# USBC.net
KiCad netlist of a schematic drawn in Altium Designer
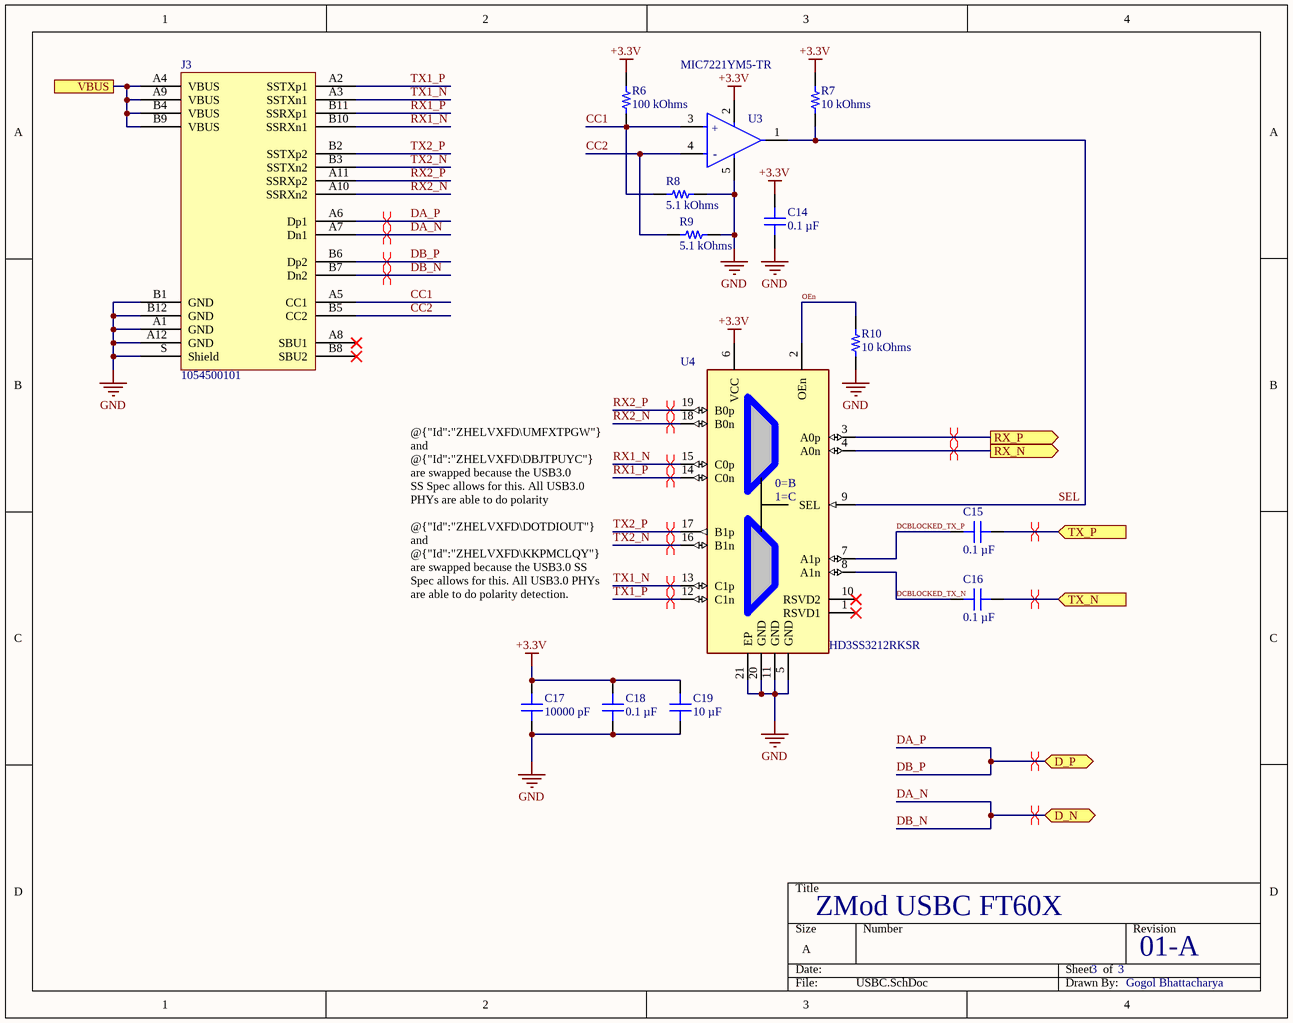
[diagram p0: USBC.SchDoc]

(export (version "E")
  (design (tool "Eeschema 10.0.6"))
  (components
    (comp (ref "C14")
      (value "0.1 µF")
      (footprint "CAP 0603_1608")
      (description "CAP CER 0.1UF 50V X7R 0603")
      (fields (field (name "PART NUMBER") "C0603C104K5RAC7411") (field (name "MANUFACTURER") "KEMET"))
      (libsource (lib "Celestial Altium Library - altium_library") (part "Capacitor"))
    )
    (comp (ref "C15")
      (value "0.1 µF")
      (footprint "CAP 0603_1608")
      (description "CAP CER 0.1UF 50V X7R 0603")
      (fields (field (name "PART NUMBER") "C0603C104K5RAC7411") (field (name "MANUFACTURER") "KEMET"))
      (libsource (lib "Celestial Altium Library - altium_library") (part "Capacitor"))
    )
    (comp (ref "C16")
      (value "0.1 µF")
      (footprint "CAP 0603_1608")
      (description "CAP CER 0.1UF 50V X7R 0603")
      (fields (field (name "PART NUMBER") "C0603C104K5RAC7411") (field (name "MANUFACTURER") "KEMET"))
      (libsource (lib "Celestial Altium Library - altium_library") (part "Capacitor"))
    )
    (comp (ref "C17")
      (value "10000 pF")
      (footprint "CAP 0603_1608")
      (description "CAP CER 0603 10NF 100V X7R")
      (fields (field (name "PART NUMBER") "C0603X103K1RAC3316") (field (name "MANUFACTURER") "KEMET"))
      (libsource (lib "Celestial Altium Library - altium_library") (part "Capacitor"))
    )
    (comp (ref "C18")
      (value "0.1 µF")
      (footprint "CAP 0603_1608")
      (description "CAP CER 0.1UF 50V X7R 0603")
      (fields (field (name "PART NUMBER") "C0603C104K5RAC7411") (field (name "MANUFACTURER") "KEMET"))
      (libsource (lib "Celestial Altium Library - altium_library") (part "Capacitor"))
    )
    (comp (ref "C19")
      (value "10 µF")
      (footprint "CAP 0603_1608")
      (description "CAP CER 10UF 16V X5R 0603")
      (fields
        (field (name "PART NUMBER") "GRT188R61C106ME13D")
        (field (name "MANUFACTURER") "Murata Electronics")
      )
      (libsource (lib "Celestial Altium Library - altium_library") (part "Capacitor"))
    )
    (comp (ref "J3")
      (value "1054500101")
      (footprint "Molex 1054500101")
      (description "CONN RCP USB3.1 TYPEC 24P SMD RA")
      (fields (field (name "MANUFACTURER") "Molex"))
      (libsource (lib "Celestial Altium Library - altium_library") (part "USB 3.0 Type C"))
    )
    (comp (ref "R6")
      (value "100 kOhms")
      (footprint "RES 0603_1608")
      (description "RES SMD 100K OHM 1% 1/4W 0603")
      (fields (field (name "PART NUMBER") "RCS0603100KFKEA") (field (name "MANUFACTURER") "Vishay Dale"))
      (libsource (lib "Celestial Altium Library - altium_library") (part "Resistor"))
    )
    (comp (ref "R7")
      (value "10 kOhms")
      (footprint "RES 0603_1608")
      (description "RES SMD 10K OHM 1% 1/10W 0603")
      (fields (field (name "PART NUMBER") "RT0603FRE0710KL") (field (name "MANUFACTURER") "Yageo"))
      (libsource (lib "Celestial Altium Library - altium_library") (part "Resistor"))
    )
    (comp (ref "R8")
      (value "5.1 kOhms")
      (footprint "RES 0603_1608")
      (description "RES 5.1K OHM 0.1% 1/10W 0603")
      (fields (field (name "PART NUMBER") "TNPW06035K10BYEN") (field (name "MANUFACTURER") "Vishay Dale"))
      (libsource (lib "Celestial Altium Library - altium_library") (part "Resistor"))
    )
    (comp (ref "R9")
      (value "5.1 kOhms")
      (footprint "RES 0603_1608")
      (description "RES 5.1K OHM 0.1% 1/10W 0603")
      (fields (field (name "PART NUMBER") "TNPW06035K10BYEN") (field (name "MANUFACTURER") "Vishay Dale"))
      (libsource (lib "Celestial Altium Library - altium_library") (part "Resistor"))
    )
    (comp (ref "R10")
      (value "10 kOhms")
      (footprint "RES 0603_1608")
      (description "RES SMD 10K OHM 1% 1/10W 0603")
      (fields (field (name "PART NUMBER") "RT0603FRE0710KL") (field (name "MANUFACTURER") "Yageo"))
      (libsource (lib "Celestial Altium Library - altium_library") (part "Resistor"))
    )
    (comp (ref "U3")
      (value "MIC7221YM5-TR")
      (footprint "FP-SOT23-5LD-PL-1-IPC_B")
      (description "Comparator, 1 Func, 10000uV Offset-Max, 75ns Response Time, CMOS, PDSO5")
      (libsource (lib "Gogol Bhattacharya (Personal)") (part "f2a62336eda9e3e8a496b1b5fa5c1ae"))
    )
    (comp (ref "U4")
      (value "HD3SS3212RKSR")
      (footprint "FP-RKS0020A-MFG")
      (description "Differential Multiplexer, 2 Func, 2 Channel, PQCC20")
      (libsource (lib "Gogol Bhattacharya (Personal)") (part "e04fd4c30857d4eb607c700c21d87fb"))
    )
  )
  (nets
    (net (code "1") (name "+3.3V") (class "Default")
      (node (ref "C14") (pin "2") (pinfunction "2_2") (pintype "passive"))
      (node (ref "C17") (pin "2") (pinfunction "2_2") (pintype "passive"))
      (node (ref "C18") (pin "1") (pinfunction "1_1") (pintype "passive"))
      (node (ref "C19") (pin "2") (pinfunction "2_2") (pintype "passive"))
      (node (ref "R6") (pin "2") (pinfunction "2_2") (pintype "passive"))
      (node (ref "R7") (pin "2") (pinfunction "2_2") (pintype "passive"))
      (node (ref "U3") (pin "2") (pinfunction "V+_2") (pintype "power_in"))
      (node (ref "U4") (pin "6") (pinfunction "VCC_6") (pintype "power_in"))
    )
    (net (code "2") (name "/CC1") (class "Default")
      (node (ref "J3") (pin "A5") (pinfunction "CC1_A5") (pintype "passive"))
      (node (ref "R6") (pin "1") (pinfunction "1_1") (pintype "passive"))
      (node (ref "R8") (pin "1") (pinfunction "1_1") (pintype "passive"))
      (node (ref "U3") (pin "3") (pinfunction "IN+_3") (pintype "tri_state"))
    )
    (net (code "3") (name "/CC2") (class "Default")
      (node (ref "J3") (pin "B5") (pinfunction "CC2_B5") (pintype "passive"))
      (node (ref "R9") (pin "1") (pinfunction "1_1") (pintype "passive"))
      (node (ref "U3") (pin "4") (pinfunction "IN-_4") (pintype "tri_state"))
    )
    (net (code "4") (name "/DA_N") (class "Default")
      (node (ref "J3") (pin "A7") (pinfunction "Dn1_A7") (pintype "passive"))
      (node (ref "J3") (pin "B7") (pinfunction "Dn2_B7") (pintype "passive"))
    )
    (net (code "5") (name "/DA_P") (class "Default")
      (node (ref "J3") (pin "A6") (pinfunction "Dp1_A6") (pintype "passive"))
      (node (ref "J3") (pin "B6") (pinfunction "Dp2_B6") (pintype "passive"))
    )
    (net (code "6") (name "/DCBLOCKED_TX_N") (class "Default")
      (node (ref "C16") (pin "1") (pinfunction "1_1") (pintype "passive"))
      (node (ref "U4") (pin "8") (pinfunction "A1n_8") (pintype "bidirectional"))
    )
    (net (code "7") (name "/DCBLOCKED_TX_P") (class "Default")
      (node (ref "C15") (pin "1") (pinfunction "1_1") (pintype "passive"))
      (node (ref "U4") (pin "7") (pinfunction "A1p_7") (pintype "bidirectional"))
    )
    (net (code "8") (name "/OEn") (class "Default")
      (node (ref "R10") (pin "2") (pinfunction "2_2") (pintype "passive"))
      (node (ref "U4") (pin "2") (pinfunction "OEn_2") (pintype "passive"))
    )
    (net (code "9") (name "/RX1_N") (class "Default")
      (node (ref "J3") (pin "B10") (pinfunction "SSRXn1_B10") (pintype "passive"))
      (node (ref "U4") (pin "15") (pinfunction "C0p_15") (pintype "bidirectional"))
    )
    (net (code "10") (name "/RX1_P") (class "Default")
      (node (ref "J3") (pin "B11") (pinfunction "SSRXp1_B11") (pintype "passive"))
      (node (ref "U4") (pin "14") (pinfunction "C0n_14") (pintype "bidirectional"))
    )
    (net (code "11") (name "/RX2_N") (class "Default")
      (node (ref "J3") (pin "A10") (pinfunction "SSRXn2_A10") (pintype "passive"))
      (node (ref "U4") (pin "18") (pinfunction "B0n_18") (pintype "bidirectional"))
    )
    (net (code "12") (name "/RX2_P") (class "Default")
      (node (ref "J3") (pin "A11") (pinfunction "SSRXp2_A11") (pintype "passive"))
      (node (ref "U4") (pin "19") (pinfunction "B0p_19") (pintype "bidirectional"))
    )
    (net (code "13") (name "/RX_N") (class "Default")
      (node (ref "U4") (pin "4") (pinfunction "A0n_4") (pintype "bidirectional"))
    )
    (net (code "14") (name "/RX_P") (class "Default")
      (node (ref "U4") (pin "3") (pinfunction "A0p_3") (pintype "bidirectional"))
    )
    (net (code "15") (name "/SEL") (class "Default")
      (node (ref "R7") (pin "1") (pinfunction "1_1") (pintype "passive"))
      (node (ref "U3") (pin "1") (pinfunction "OUT_1") (pintype "passive"))
      (node (ref "U4") (pin "9") (pinfunction "SEL_9") (pintype "input"))
    )
    (net (code "16") (name "/TX1_N") (class "Default")
      (node (ref "J3") (pin "A3") (pinfunction "SSTXn1_A3") (pintype "passive"))
      (node (ref "U4") (pin "13") (pinfunction "C1p_13") (pintype "bidirectional"))
    )
    (net (code "17") (name "/TX1_P") (class "Default")
      (node (ref "J3") (pin "A2") (pinfunction "SSTXp1_A2") (pintype "passive"))
      (node (ref "U4") (pin "12") (pinfunction "C1n_12") (pintype "bidirectional"))
    )
    (net (code "18") (name "/TX2_N") (class "Default")
      (node (ref "J3") (pin "B3") (pinfunction "SSTXn2_B3") (pintype "passive"))
      (node (ref "U4") (pin "16") (pinfunction "B1n_16") (pintype "bidirectional"))
    )
    (net (code "19") (name "/TX2_P") (class "Default")
      (node (ref "J3") (pin "B2") (pinfunction "SSTXp2_B2") (pintype "passive"))
      (node (ref "U4") (pin "17") (pinfunction "B1p_17") (pintype "output"))
    )
    (net (code "20") (name "/TX_N") (class "Default")
      (node (ref "C16") (pin "2") (pinfunction "2_2") (pintype "passive"))
    )
    (net (code "21") (name "/TX_P") (class "Default")
      (node (ref "C15") (pin "2") (pinfunction "2_2") (pintype "passive"))
    )
    (net (code "22") (name "/VBUS") (class "Default")
      (node (ref "J3") (pin "A4") (pinfunction "VBUS_A4") (pintype "passive"))
      (node (ref "J3") (pin "A9") (pinfunction "VBUS_A9") (pintype "passive"))
      (node (ref "J3") (pin "B4") (pinfunction "VBUS_B4") (pintype "passive"))
      (node (ref "J3") (pin "B9") (pinfunction "VBUS_B9") (pintype "passive"))
    )
    (net (code "23") (name "GND") (class "Default")
      (node (ref "C14") (pin "1") (pinfunction "1_1") (pintype "passive"))
      (node (ref "C17") (pin "1") (pinfunction "1_1") (pintype "passive"))
      (node (ref "C18") (pin "2") (pinfunction "2_2") (pintype "passive"))
      (node (ref "C19") (pin "1") (pinfunction "1_1") (pintype "passive"))
      (node (ref "J3") (pin "A1") (pinfunction "GND_A1") (pintype "passive"))
      (node (ref "J3") (pin "A12") (pinfunction "GND_A12") (pintype "passive"))
      (node (ref "J3") (pin "B1") (pinfunction "GND_B1") (pintype "passive"))
      (node (ref "J3") (pin "B12") (pinfunction "GND_B12") (pintype "passive"))
      (node (ref "J3") (pin "S") (pinfunction "Shield_S") (pintype "passive"))
      (node (ref "R10") (pin "1") (pinfunction "1_1") (pintype "passive"))
      (node (ref "R8") (pin "2") (pinfunction "2_2") (pintype "passive"))
      (node (ref "R9") (pin "2") (pinfunction "2_2") (pintype "passive"))
      (node (ref "U3") (pin "5") (pinfunction "V-_5") (pintype "power_in"))
      (node (ref "U4") (pin "11") (pinfunction "GND_11") (pintype "power_in"))
      (node (ref "U4") (pin "20") (pinfunction "GND_20") (pintype "power_in"))
      (node (ref "U4") (pin "21") (pinfunction "EP_21") (pintype "power_in"))
      (node (ref "U4") (pin "5") (pinfunction "GND_5") (pintype "power_in"))
    )
    (net (code "24") (name "unconnected-(J3-SBU1-PadA8)") (class "Default")
      (node (ref "J3") (pin "A8") (pinfunction "SBU1_A8") (pintype "passive+no_connect"))
    )
    (net (code "25") (name "unconnected-(J3-SBU2-PadB8)") (class "Default")
      (node (ref "J3") (pin "B8") (pinfunction "SBU2_B8") (pintype "passive+no_connect"))
    )
    (net (code "26") (name "unconnected-(U4-RSVD1-Pad1)") (class "Default")
      (node (ref "U4") (pin "1") (pinfunction "RSVD1_1") (pintype "passive+no_connect"))
    )
    (net (code "27") (name "unconnected-(U4-RSVD2-Pad10)") (class "Default")
      (node (ref "U4") (pin "10") (pinfunction "RSVD2_10") (pintype "passive+no_connect"))
    )
  )
)
